# UMR2_CS01_ADAPTER.net
KiCad netlist of a schematic drawn in EAGLE
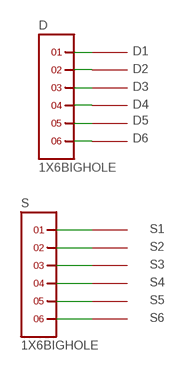
[diagram p0: schematic, sheet 1]

(export (version "E")
  (design (tool "Eeschema 10.0.6"))
  (components
    (comp (ref "D")
      (value "1X6BIGHOLE")
      (footprint "eagle-import:1X6")
      (libsource (lib "eagle-import") (part "1X6BIGHOLE"))
    )
    (comp (ref "D1")
      (value "SMD_PAD")
      (footprint "eagle-import:SMDPAD_1X2")
      (libsource (lib "eagle-import") (part "SMD_PAD"))
    )
    (comp (ref "D2")
      (value "SMD_PAD")
      (footprint "eagle-import:SMDPAD_1X2")
      (libsource (lib "eagle-import") (part "SMD_PAD"))
    )
    (comp (ref "D3")
      (value "SMD_PAD")
      (footprint "eagle-import:SMDPAD_1X2")
      (libsource (lib "eagle-import") (part "SMD_PAD"))
    )
    (comp (ref "D4")
      (value "SMD_PAD")
      (footprint "eagle-import:SMDPAD_1X2")
      (libsource (lib "eagle-import") (part "SMD_PAD"))
    )
    (comp (ref "D5")
      (value "SMD_PAD")
      (footprint "eagle-import:SMDPAD_1X2")
      (libsource (lib "eagle-import") (part "SMD_PAD"))
    )
    (comp (ref "D6")
      (value "SMD_PAD")
      (footprint "eagle-import:SMDPAD_1X2")
      (libsource (lib "eagle-import") (part "SMD_PAD"))
    )
    (comp (ref "S")
      (value "1X6BIGHOLE")
      (footprint "eagle-import:1X6")
      (libsource (lib "eagle-import") (part "1X6BIGHOLE"))
    )
    (comp (ref "S1")
      (value "SMD_PAD")
      (footprint "eagle-import:SMDPAD_1X2")
      (libsource (lib "eagle-import") (part "SMD_PAD"))
    )
    (comp (ref "S2")
      (value "SMD_PAD")
      (footprint "eagle-import:SMDPAD_1X2")
      (libsource (lib "eagle-import") (part "SMD_PAD"))
    )
    (comp (ref "S3")
      (value "SMD_PAD")
      (footprint "eagle-import:SMDPAD_1X2")
      (libsource (lib "eagle-import") (part "SMD_PAD"))
    )
    (comp (ref "S4")
      (value "SMD_PAD")
      (footprint "eagle-import:SMDPAD_1X2")
      (libsource (lib "eagle-import") (part "SMD_PAD"))
    )
    (comp (ref "S5")
      (value "SMD_PAD")
      (footprint "eagle-import:SMDPAD_1X2")
      (libsource (lib "eagle-import") (part "SMD_PAD"))
    )
    (comp (ref "S6")
      (value "SMD_PAD")
      (footprint "eagle-import:SMDPAD_1X2")
      (libsource (lib "eagle-import") (part "SMD_PAD"))
    )
  )
  (nets
    (net (code "1") (name "Net-(D1->NAME)") (class "Default")
      (node (ref "D") (pin "1") (pinfunction "1_1") (pintype "bidirectional"))
      (node (ref "D1") (pin "P$1") (pinfunction ">NAME_P$1") (pintype "bidirectional"))
    )
    (net (code "2") (name "Net-(D2->NAME)") (class "Default")
      (node (ref "D") (pin "2") (pinfunction "2_2") (pintype "bidirectional"))
      (node (ref "D2") (pin "P$1") (pinfunction ">NAME_P$1") (pintype "bidirectional"))
    )
    (net (code "3") (name "Net-(D3->NAME)") (class "Default")
      (node (ref "D") (pin "3") (pinfunction "3_3") (pintype "bidirectional"))
      (node (ref "D3") (pin "P$1") (pinfunction ">NAME_P$1") (pintype "bidirectional"))
    )
    (net (code "4") (name "Net-(D4->NAME)") (class "Default")
      (node (ref "D") (pin "4") (pinfunction "4_4") (pintype "bidirectional"))
      (node (ref "D4") (pin "P$1") (pinfunction ">NAME_P$1") (pintype "bidirectional"))
    )
    (net (code "5") (name "Net-(D5->NAME)") (class "Default")
      (node (ref "D") (pin "5") (pinfunction "5_5") (pintype "bidirectional"))
      (node (ref "D5") (pin "P$1") (pinfunction ">NAME_P$1") (pintype "bidirectional"))
    )
    (net (code "6") (name "Net-(D6->NAME)") (class "Default")
      (node (ref "D") (pin "6") (pinfunction "6_6") (pintype "bidirectional"))
      (node (ref "D6") (pin "P$1") (pinfunction ">NAME_P$1") (pintype "bidirectional"))
    )
    (net (code "7") (name "Net-(S1->NAME)") (class "Default")
      (node (ref "S") (pin "1") (pinfunction "1_1") (pintype "bidirectional"))
      (node (ref "S1") (pin "P$1") (pinfunction ">NAME_P$1") (pintype "bidirectional"))
    )
    (net (code "8") (name "Net-(S2->NAME)") (class "Default")
      (node (ref "S") (pin "2") (pinfunction "2_2") (pintype "bidirectional"))
      (node (ref "S2") (pin "P$1") (pinfunction ">NAME_P$1") (pintype "bidirectional"))
    )
    (net (code "9") (name "Net-(S3->NAME)") (class "Default")
      (node (ref "S") (pin "3") (pinfunction "3_3") (pintype "bidirectional"))
      (node (ref "S3") (pin "P$1") (pinfunction ">NAME_P$1") (pintype "bidirectional"))
    )
    (net (code "10") (name "Net-(S4->NAME)") (class "Default")
      (node (ref "S") (pin "4") (pinfunction "4_4") (pintype "bidirectional"))
      (node (ref "S4") (pin "P$1") (pinfunction ">NAME_P$1") (pintype "bidirectional"))
    )
    (net (code "11") (name "Net-(S5->NAME)") (class "Default")
      (node (ref "S") (pin "5") (pinfunction "5_5") (pintype "bidirectional"))
      (node (ref "S5") (pin "P$1") (pinfunction ">NAME_P$1") (pintype "bidirectional"))
    )
    (net (code "12") (name "Net-(S6->NAME)") (class "Default")
      (node (ref "S") (pin "6") (pinfunction "6_6") (pintype "bidirectional"))
      (node (ref "S6") (pin "P$1") (pinfunction ">NAME_P$1") (pintype "bidirectional"))
    )
  )
)
